# iot_inventory_mote.net
KiCad netlist of a schematic drawn in EAGLE
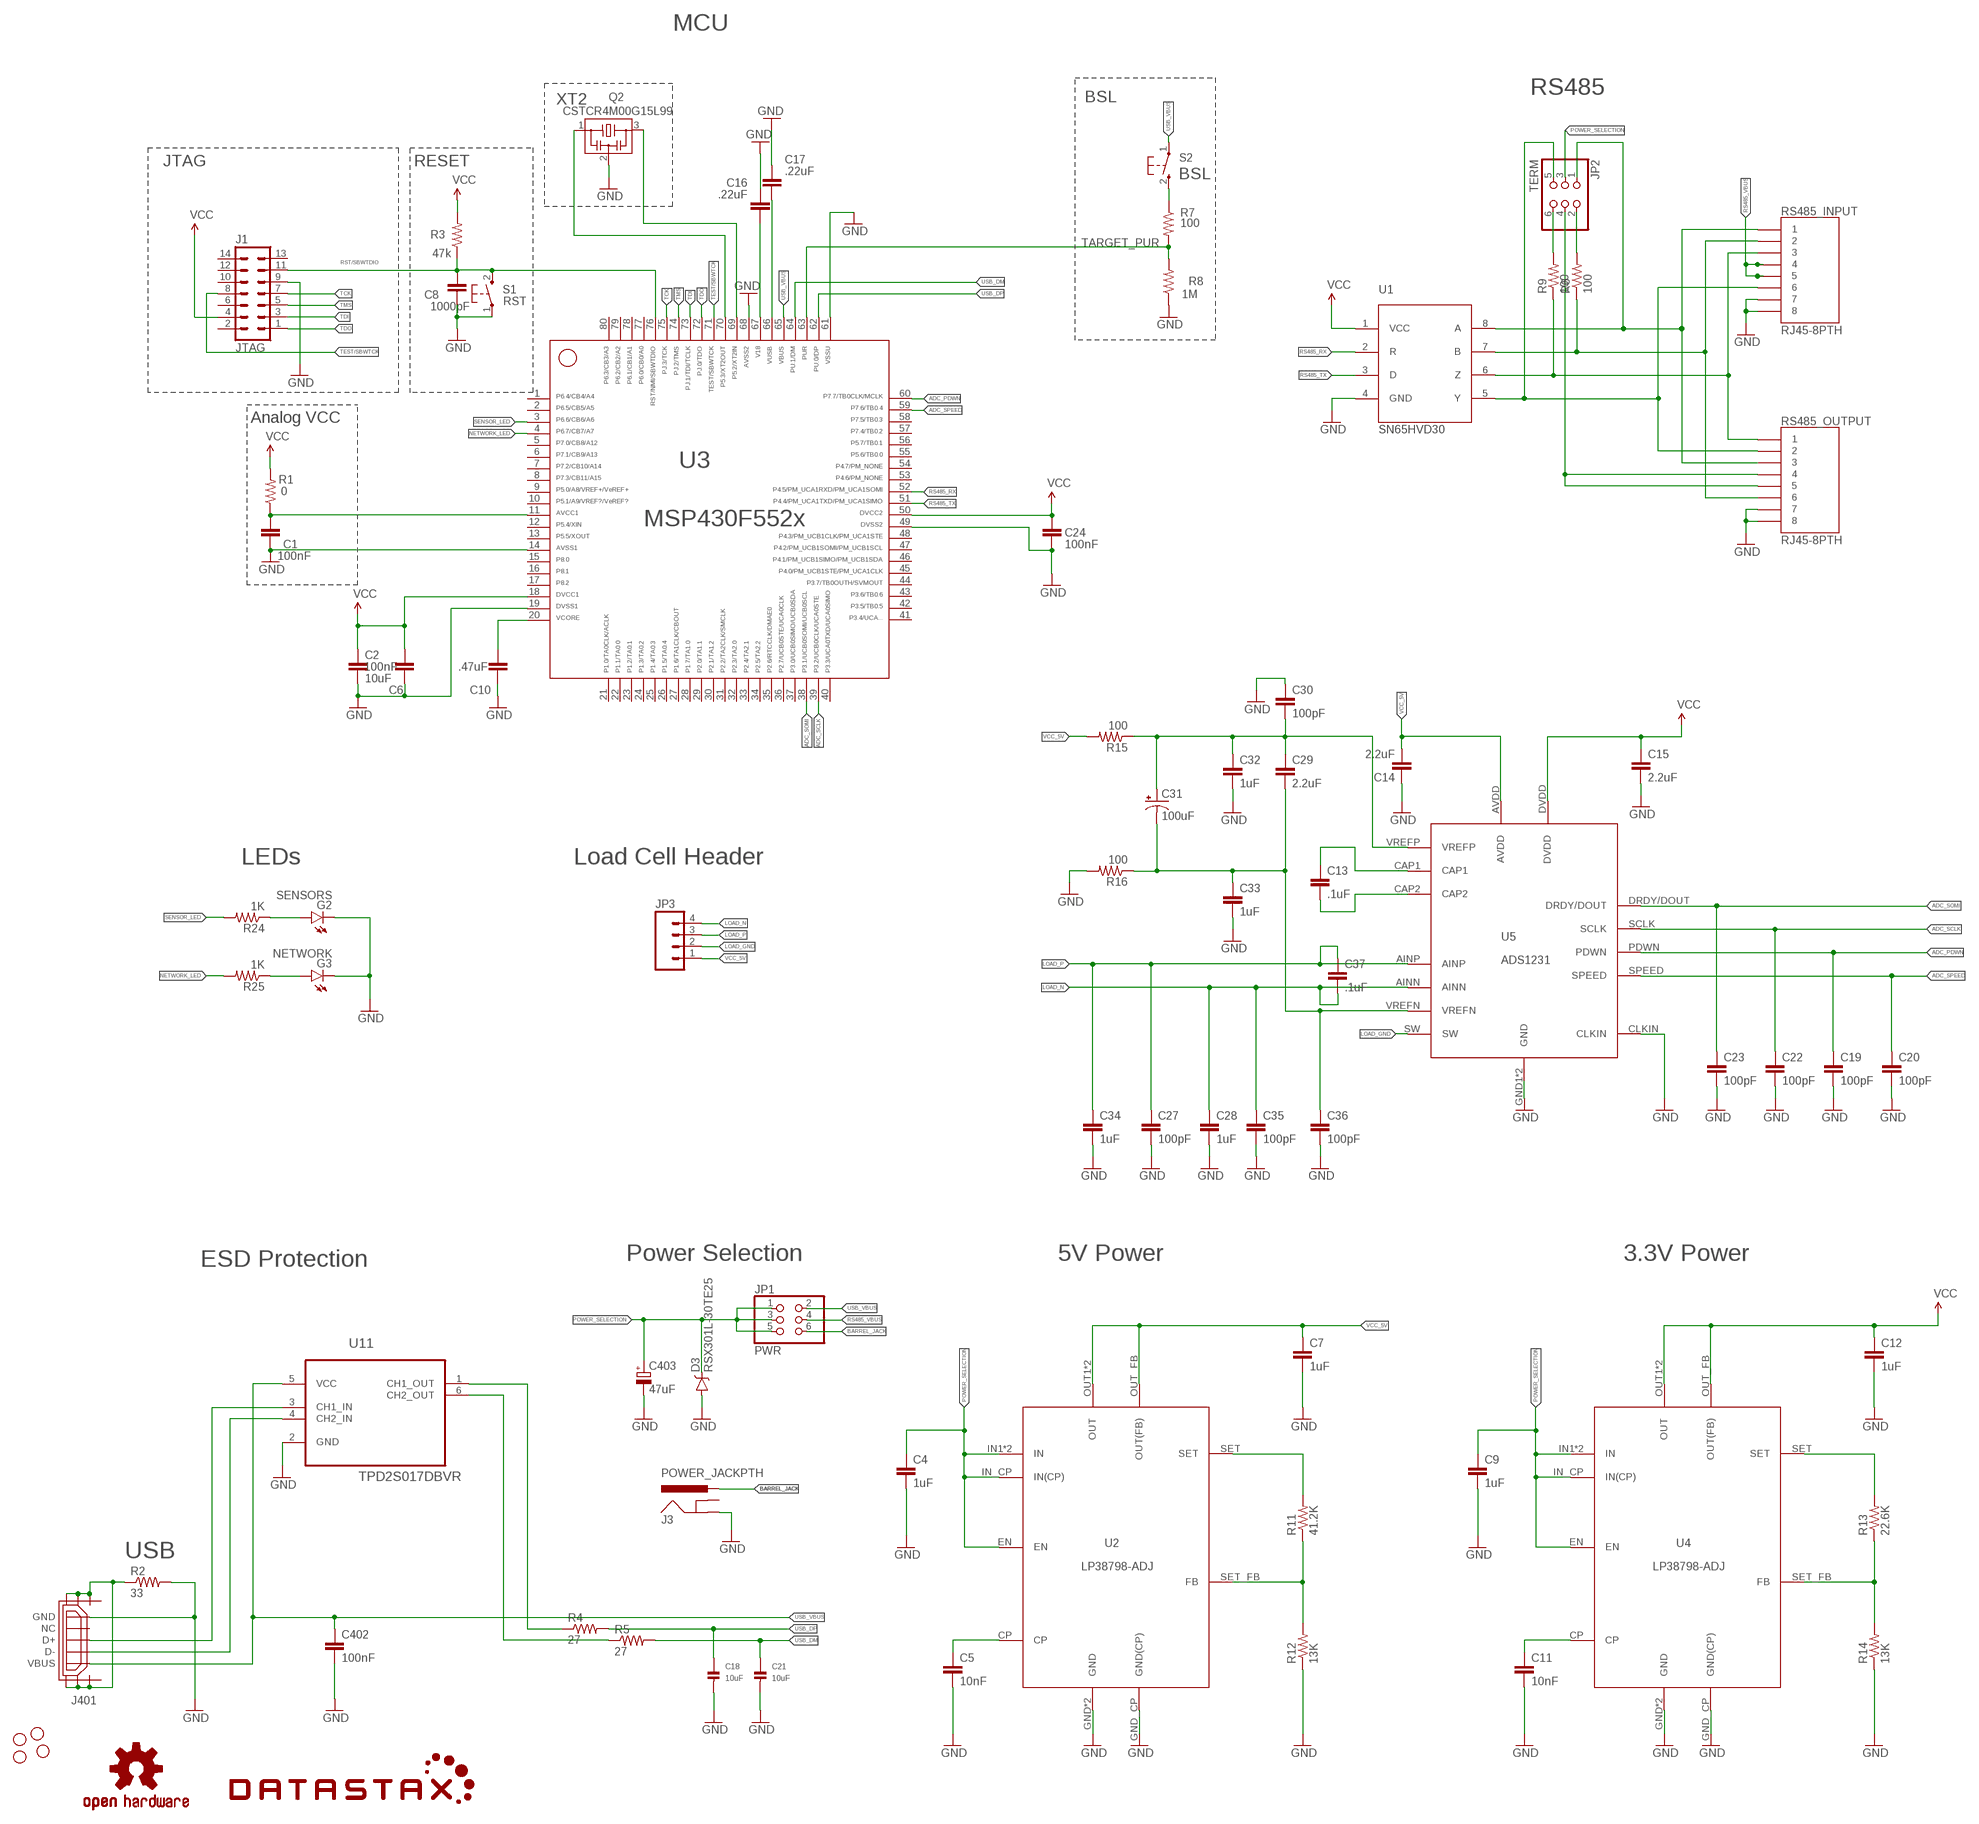
[diagram p0: schematic, sheet 1]

(export (version "E")
  (design (tool "Eeschema 10.0.6"))
  (components
    (comp (ref "C1")
      (value "100nF")
      (footprint "eagle-import:0402-CAP")
      (libsource (lib "eagle-import") (part "CAP0402-CAP"))
    )
    (comp (ref "C2")
      (value "10uF")
      (footprint "eagle-import:0402-CAP")
      (libsource (lib "eagle-import") (part "CAP0402-CAP"))
    )
    (comp (ref "C4")
      (value "1uF")
      (footprint "eagle-import:0402-CAP")
      (libsource (lib "eagle-import") (part "CAP0402-CAP"))
    )
    (comp (ref "C5")
      (value "10nF")
      (footprint "eagle-import:0402-CAP")
      (libsource (lib "eagle-import") (part "CAP0402-CAP"))
    )
    (comp (ref "C6")
      (value "100nF")
      (footprint "eagle-import:0402-CAP")
      (libsource (lib "eagle-import") (part "CAP0402-CAP"))
    )
    (comp (ref "C7")
      (value "1uF")
      (footprint "eagle-import:0402-CAP")
      (libsource (lib "eagle-import") (part "CAP0402-CAP"))
    )
    (comp (ref "C8")
      (value "1000pF")
      (footprint "eagle-import:0402-CAP")
      (fields (field (name "MF") "TDK") (field (name "MPN") "C1005X7R1H102K050BA"))
      (libsource (lib "eagle-import") (part "CAP0402-CAP"))
    )
    (comp (ref "C9")
      (value "1uF")
      (footprint "eagle-import:0402-CAP")
      (libsource (lib "eagle-import") (part "CAP0402-CAP"))
    )
    (comp (ref "C10")
      (value ".47uF")
      (footprint "eagle-import:0402-CAP")
      (libsource (lib "eagle-import") (part "CAP0402-CAP"))
    )
    (comp (ref "C11")
      (value "10nF")
      (footprint "eagle-import:0402-CAP")
      (libsource (lib "eagle-import") (part "CAP0402-CAP"))
    )
    (comp (ref "C12")
      (value "1uF")
      (footprint "eagle-import:0402-CAP")
      (libsource (lib "eagle-import") (part "CAP0402-CAP"))
    )
    (comp (ref "C13")
      (value ".1uF")
      (footprint "eagle-import:1210")
      (libsource (lib "eagle-import") (part "CAP1210"))
    )
    (comp (ref "C14")
      (value "2.2uF")
      (footprint "eagle-import:0402-CAP")
      (libsource (lib "eagle-import") (part "CAP0402-CAP"))
    )
    (comp (ref "C15")
      (value "2.2uF")
      (footprint "eagle-import:0402-CAP")
      (libsource (lib "eagle-import") (part "CAP0402-CAP"))
    )
    (comp (ref "C16")
      (value ".22uF")
      (footprint "eagle-import:0402-CAP")
      (libsource (lib "eagle-import") (part "CAP0402-CAP"))
    )
    (comp (ref "C17")
      (value ".22uF")
      (footprint "eagle-import:0402-CAP")
      (libsource (lib "eagle-import") (part "CAP0402-CAP"))
    )
    (comp (ref "C18")
      (value "10uF")
      (footprint "eagle-import:0603")
      (fields (field (name "MPN") "06035A100FAT2A"))
      (libsource (lib "eagle-import") (part "CAP_CERAMIC0603"))
    )
    (comp (ref "C19")
      (value "100pF")
      (footprint "eagle-import:0805")
      (libsource (lib "eagle-import") (part "CAP0805"))
    )
    (comp (ref "C20")
      (value "100pF")
      (footprint "eagle-import:0805")
      (libsource (lib "eagle-import") (part "CAP0805"))
    )
    (comp (ref "C21")
      (value "10uF")
      (footprint "eagle-import:0603")
      (fields (field (name "MPN") "06035A100FAT2A"))
      (libsource (lib "eagle-import") (part "CAP_CERAMIC0603"))
    )
    (comp (ref "C22")
      (value "100pF")
      (footprint "eagle-import:0805")
      (libsource (lib "eagle-import") (part "CAP0805"))
    )
    (comp (ref "C23")
      (value "100pF")
      (footprint "eagle-import:0805")
      (libsource (lib "eagle-import") (part "CAP0805"))
    )
    (comp (ref "C24")
      (value "100nF")
      (footprint "eagle-import:0402-CAP")
      (libsource (lib "eagle-import") (part "CAP0402-CAP"))
    )
    (comp (ref "C27")
      (value "100pF")
      (footprint "eagle-import:0603-CAP")
      (libsource (lib "eagle-import") (part "CAP0603-CAP"))
    )
    (comp (ref "C28")
      (value "1uF")
      (footprint "eagle-import:0805")
      (libsource (lib "eagle-import") (part "CAP0805"))
    )
    (comp (ref "C29")
      (value "2.2uF")
      (footprint "eagle-import:0402-CAP")
      (libsource (lib "eagle-import") (part "CAP0402-CAP"))
    )
    (comp (ref "C30")
      (value "100pF")
      (footprint "eagle-import:0603-CAP")
      (libsource (lib "eagle-import") (part "CAP0603-CAP"))
    )
    (comp (ref "C31")
      (value "100uF")
      (footprint "eagle-import:EIA7343")
      (libsource (lib "eagle-import") (part "CAP_POL7343"))
    )
    (comp (ref "C32")
      (value "1uF")
      (footprint "eagle-import:0805")
      (libsource (lib "eagle-import") (part "CAP0805"))
    )
    (comp (ref "C33")
      (value "1uF")
      (footprint "eagle-import:0805")
      (libsource (lib "eagle-import") (part "CAP0805"))
    )
    (comp (ref "C34")
      (value "1uF")
      (footprint "eagle-import:0805")
      (libsource (lib "eagle-import") (part "CAP0805"))
    )
    (comp (ref "C35")
      (value "100pF")
      (footprint "eagle-import:0603-CAP")
      (libsource (lib "eagle-import") (part "CAP0603-CAP"))
    )
    (comp (ref "C36")
      (value "100pF")
      (footprint "eagle-import:0603-CAP")
      (libsource (lib "eagle-import") (part "CAP0603-CAP"))
    )
    (comp (ref "C37")
      (value ".1uF")
      (footprint "eagle-import:1210")
      (libsource (lib "eagle-import") (part "CAP1210"))
    )
    (comp (ref "C402")
      (value "100nF")
      (footprint "eagle-import:0402-CAP")
      (fields (field (name "MPN") "100NA100MEFC12.5X25"))
      (libsource (lib "eagle-import") (part "CAP0402-CAP"))
    )
    (comp (ref "C403")
      (value "47uF")
      (footprint "eagle-import:A_3216-18R")
      (libsource (lib "eagle-import") (part "CPOL-EUA/3216-18R"))
    )
    (comp (ref "D3")
      (value "RSX301L-30TE25")
      (footprint "eagle-import:SMA-DIODE")
      (libsource (lib "eagle-import") (part "MBRA140"))
    )
    (comp (ref "G2")
      (value "SENSORS")
      (footprint "eagle-import:LED-0603")
      (libsource (lib "eagle-import") (part "LED0603"))
    )
    (comp (ref "G3")
      (value "NETWORK")
      (footprint "eagle-import:LED-0603")
      (libsource (lib "eagle-import") (part "LED0603"))
    )
    (comp (ref "J1")
      (value "JTAG")
      (footprint "eagle-import:ML14")
      (fields (field (name "MF") "SULLINS") (field (name "MPN") "SBH11-PBPC-D07-ST-BK"))
      (libsource (lib "eagle-import") (part "ML14"))
    )
    (comp (ref "J3")
      (value "POWER_JACKPTH")
      (footprint "eagle-import:POWER_JACK_PTH")
      (libsource (lib "eagle-import") (part "POWER_JACKPTH"))
    )
    (comp (ref "J401")
      (value "USB_MICRO_FLIPPED")
      (footprint "eagle-import:HIROSE-ZX62R-B-5P")
      (fields (field (name "MF") "HIROSE") (field (name "MPN") "ZX62R-B-5P"))
      (libsource (lib "eagle-import") (part "USB_MICRO_FLIPPED"))
    )
    (comp (ref "JP1")
      (value "PWR")
      (footprint "eagle-import:2X03")
      (libsource (lib "eagle-import") (part "PINHD-2X3"))
    )
    (comp (ref "JP2")
      (value "TERM")
      (footprint "eagle-import:2X03")
      (libsource (lib "eagle-import") (part "PINHD-2X3"))
    )
    (comp (ref "JP3")
      (value "M04SCREW")
      (footprint "eagle-import:SCREWTERMINAL-3.5MM-4")
      (libsource (lib "eagle-import") (part "M04SCREW"))
    )
    (comp (ref "LOGO1")
      (value "OSHW-LOGOL")
      (footprint "eagle-import:OSHW-LOGO-L")
      (libsource (lib "eagle-import") (part "OSHW-LOGOL"))
    )
    (comp (ref "Q2")
      (value "CSTCR4M00G15L99")
      (footprint "eagle-import:MURATA-FILTER_CSTCR")
      (fields (field (name "MPN") "CSTCR6M00G53-R0") (field (name "MF") "MURATA"))
      (libsource (lib "eagle-import") (part "MURATA-FILTER_CSTCR6M00G53Z"))
    )
    (comp (ref "R1")
      (value "0")
      (footprint "eagle-import:R0402")
      (libsource (lib "eagle-import") (part "R-US_R0402"))
    )
    (comp (ref "R2")
      (value "33")
      (footprint "eagle-import:0402-RES")
      (libsource (lib "eagle-import") (part "RESISTOR0402-RES"))
    )
    (comp (ref "R3")
      (value "47k")
      (footprint "eagle-import:R0402")
      (fields (field (name "MF") "PANASONIC ") (field (name "MPN") "ERJ-2RKF4702X"))
      (libsource (lib "eagle-import") (part "R-US_R0402"))
    )
    (comp (ref "R4")
      (value "27")
      (footprint "eagle-import:0402-RES")
      (libsource (lib "eagle-import") (part "RESISTOR0402-RES"))
    )
    (comp (ref "R5")
      (value "27")
      (footprint "eagle-import:0402-RES")
      (libsource (lib "eagle-import") (part "RESISTOR0402-RES"))
    )
    (comp (ref "R6")
      (value "100")
      (footprint "eagle-import:0402-RES")
      (libsource (lib "eagle-import") (part "RESISTOR0402-RES"))
    )
    (comp (ref "R7")
      (value "100")
      (footprint "eagle-import:R0402")
      (libsource (lib "eagle-import") (part "R-US_R0402"))
    )
    (comp (ref "R8")
      (value "1M")
      (footprint "eagle-import:R0402")
      (libsource (lib "eagle-import") (part "R-US_R0402"))
    )
    (comp (ref "R9")
      (value "100")
      (footprint "eagle-import:0402-RES")
      (libsource (lib "eagle-import") (part "RESISTOR0402-RES"))
    )
    (comp (ref "R11")
      (value "41.2K")
      (footprint "eagle-import:0402-RES")
      (libsource (lib "eagle-import") (part "RESISTOR0402-RES"))
    )
    (comp (ref "R12")
      (value "13K")
      (footprint "eagle-import:0402-RES")
      (libsource (lib "eagle-import") (part "RESISTOR0402-RES"))
    )
    (comp (ref "R13")
      (value "22.6K")
      (footprint "eagle-import:0402-RES")
      (libsource (lib "eagle-import") (part "RESISTOR0402-RES"))
    )
    (comp (ref "R14")
      (value "13K")
      (footprint "eagle-import:0402-RES")
      (libsource (lib "eagle-import") (part "RESISTOR0402-RES"))
    )
    (comp (ref "R15")
      (value "100")
      (footprint "eagle-import:0402-RES")
      (libsource (lib "eagle-import") (part "RESISTOR0402-RES"))
    )
    (comp (ref "R16")
      (value "100")
      (footprint "eagle-import:0402-RES")
      (libsource (lib "eagle-import") (part "RESISTOR0402-RES"))
    )
    (comp (ref "R24")
      (value "1K")
      (footprint "eagle-import:0402-RES")
      (fields (field (name "MF") "PANASONIC") (field (name "MPN") "ERJ-2RKF1001X"))
      (libsource (lib "eagle-import") (part "RESISTOR0402-RES"))
    )
    (comp (ref "R25")
      (value "1K")
      (footprint "eagle-import:0402-RES")
      (fields (field (name "MF") "PANASONIC") (field (name "MPN") "ERJ-2RKF1001X"))
      (libsource (lib "eagle-import") (part "RESISTOR0402-RES"))
    )
    (comp (ref "RS485_INPUT")
      (value "RJ45-8PTH")
      (footprint "eagle-import:RJ45-8")
      (fields (field (name "MF") "FCI") (field (name "MPN") "54602-908LF"))
      (libsource (lib "eagle-import") (part "RJ45-8PTH"))
    )
    (comp (ref "RS485_OUTPUT")
      (value "RJ45-8PTH")
      (footprint "eagle-import:RJ45-8")
      (fields (field (name "MF") "FCI") (field (name "MPN") "54602-908LF"))
      (libsource (lib "eagle-import") (part "RJ45-8PTH"))
    )
    (comp (ref "S1")
      (value "RST")
      (footprint "eagle-import:PBTH")
      (fields (field (name "MF") "PANASONIC ") (field (name "MPN") "EVQ-11L05R"))
      (libsource (lib "eagle-import") (part "PB"))
    )
    (comp (ref "S2")
      (value "BSL")
      (footprint "eagle-import:PBTH")
      (libsource (lib "eagle-import") (part "PB"))
    )
    (comp (ref "STANDOFF1")
      (value "STAND-OFF")
      (footprint "eagle-import:STAND-OFF")
      (libsource (lib "eagle-import") (part "STAND-OFF"))
    )
    (comp (ref "STANDOFF2")
      (value "STAND-OFF")
      (footprint "eagle-import:STAND-OFF")
      (libsource (lib "eagle-import") (part "STAND-OFF"))
    )
    (comp (ref "STANDOFF3")
      (value "STAND-OFF")
      (footprint "eagle-import:STAND-OFF")
      (libsource (lib "eagle-import") (part "STAND-OFF"))
    )
    (comp (ref "STANDOFF4")
      (value "STAND-OFF")
      (footprint "eagle-import:STAND-OFF")
      (libsource (lib "eagle-import") (part "STAND-OFF"))
    )
    (comp (ref "U$1")
      (value "DATASTAX_LOGO")
      (footprint "eagle-import:DATASTAX_LOGO")
      (libsource (lib "eagle-import") (part "DATASTAX_LOGO"))
    )
    (comp (ref "U1")
      (value "SN65HVD30")
      (footprint "eagle-import:SOIC8")
      (fields (field (name "MF") "TI") (field (name "MPN") "SN65HVD3082EDR"))
      (libsource (lib "eagle-import") (part "SN65HVD30"))
    )
    (comp (ref "U2")
      (value "LP38798-ADJ")
      (footprint "eagle-import:WSON12")
      (fields (field (name "MF") "TI") (field (name "MPN") "LP38798SD-ADJ/NOPB"))
      (libsource (lib "eagle-import") (part "LP38798-ADJ"))
    )
    (comp (ref "U3")
      (value "MSP430F5529IPNR")
      (footprint "eagle-import:PN80")
      (fields (field (name "MF") "TI"))
      (libsource (lib "eagle-import") (part "F552X---PN80"))
    )
    (comp (ref "U4")
      (value "LP38798-ADJ")
      (footprint "eagle-import:WSON12")
      (fields (field (name "MF") "TI") (field (name "MPN") "LP38798SD-ADJ/NOPB"))
      (libsource (lib "eagle-import") (part "LP38798-ADJ"))
    )
    (comp (ref "U5")
      (value "ADS1231")
      (footprint "eagle-import:ADS1231")
      (fields (field (name "MF") "TI") (field (name "MPN") "ADS1231ID"))
      (libsource (lib "eagle-import") (part "ADS1231"))
    )
    (comp (ref "U11")
      (value "TPD2S017DBVR")
      (footprint "eagle-import:SOT95P280X145-6N")
      (fields (field (name "MF") "TI"))
      (libsource (lib "eagle-import") (part "TPD2S017DBVR"))
    )
  )
  (nets
    (net (code "1") (name "ADC_PDWN") (class "Default")
      (node (ref "C19") (pin "1") (pinfunction "1_1") (pintype "passive"))
      (node (ref "U3") (pin "60") (pinfunction "60_60") (pintype "bidirectional"))
      (node (ref "U5") (pin "PDWN") (pinfunction "PDWN_PDWN") (pintype "input"))
    )
    (net (code "2") (name "ADC_SCLK") (class "Default")
      (node (ref "C22") (pin "1") (pinfunction "1_1") (pintype "passive"))
      (node (ref "U3") (pin "39") (pinfunction "39_39") (pintype "bidirectional"))
      (node (ref "U5") (pin "SCLK") (pinfunction "SCLK_SCLK") (pintype "input"))
    )
    (net (code "3") (name "ADC_SOMI") (class "Default")
      (node (ref "C23") (pin "1") (pinfunction "1_1") (pintype "passive"))
      (node (ref "U3") (pin "38") (pinfunction "38_38") (pintype "bidirectional"))
      (node (ref "U5") (pin "DRDY/DOUT") (pinfunction "DRDY/DOUT_DRDY/DOUT") (pintype "output"))
    )
    (net (code "4") (name "ADC_SPEED") (class "Default")
      (node (ref "C20") (pin "1") (pinfunction "1_1") (pintype "passive"))
      (node (ref "U3") (pin "59") (pinfunction "59_59") (pintype "bidirectional"))
      (node (ref "U5") (pin "SPEED") (pinfunction "SPEED_SPEED") (pintype "input"))
    )
    (net (code "5") (name "BARREL_JACK") (class "Default")
      (node (ref "J3") (pin "PWR") (pinfunction "PWR_PWR") (pintype "bidirectional"))
      (node (ref "JP1") (pin "6") (pinfunction "6_6") (pintype "passive"))
    )
    (net (code "6") (name "GND") (class "Default")
      (node (ref "C1") (pin "2") (pinfunction "2_2") (pintype "passive"))
      (node (ref "C10") (pin "2") (pinfunction "2_2") (pintype "passive"))
      (node (ref "C11") (pin "2") (pinfunction "2_2") (pintype "passive"))
      (node (ref "C12") (pin "2") (pinfunction "2_2") (pintype "passive"))
      (node (ref "C14") (pin "1") (pinfunction "1_1") (pintype "passive"))
      (node (ref "C15") (pin "2") (pinfunction "2_2") (pintype "passive"))
      (node (ref "C16") (pin "2") (pinfunction "2_2") (pintype "passive"))
      (node (ref "C17") (pin "2") (pinfunction "2_2") (pintype "passive"))
      (node (ref "C18") (pin "2") (pinfunction "P$2_2") (pintype "passive"))
      (node (ref "C19") (pin "2") (pinfunction "2_2") (pintype "passive"))
      (node (ref "C2") (pin "2") (pinfunction "2_2") (pintype "passive"))
      (node (ref "C20") (pin "2") (pinfunction "2_2") (pintype "passive"))
      (node (ref "C21") (pin "2") (pinfunction "P$2_2") (pintype "passive"))
      (node (ref "C22") (pin "2") (pinfunction "2_2") (pintype "passive"))
      (node (ref "C23") (pin "2") (pinfunction "2_2") (pintype "passive"))
      (node (ref "C24") (pin "2") (pinfunction "2_2") (pintype "passive"))
      (node (ref "C27") (pin "2") (pinfunction "2_2") (pintype "passive"))
      (node (ref "C28") (pin "2") (pinfunction "2_2") (pintype "passive"))
      (node (ref "C30") (pin "1") (pinfunction "1_1") (pintype "passive"))
      (node (ref "C32") (pin "2") (pinfunction "2_2") (pintype "passive"))
      (node (ref "C33") (pin "2") (pinfunction "2_2") (pintype "passive"))
      (node (ref "C34") (pin "2") (pinfunction "2_2") (pintype "passive"))
      (node (ref "C35") (pin "2") (pinfunction "2_2") (pintype "passive"))
      (node (ref "C36") (pin "2") (pinfunction "2_2") (pintype "passive"))
      (node (ref "C4") (pin "2") (pinfunction "2_2") (pintype "passive"))
      (node (ref "C402") (pin "2") (pinfunction "2_2") (pintype "passive"))
      (node (ref "C403") (pin "-") (pinfunction "-_-") (pintype "passive"))
      (node (ref "C5") (pin "2") (pinfunction "2_2") (pintype "passive"))
      (node (ref "C6") (pin "2") (pinfunction "2_2") (pintype "passive"))
      (node (ref "C7") (pin "2") (pinfunction "2_2") (pintype "passive"))
      (node (ref "C8") (pin "2") (pinfunction "2_2") (pintype "passive"))
      (node (ref "C9") (pin "2") (pinfunction "2_2") (pintype "passive"))
      (node (ref "D3") (pin "A") (pinfunction "A_A") (pintype "passive"))
      (node (ref "G2") (pin "C") (pinfunction "C_C") (pintype "passive"))
      (node (ref "G3") (pin "C") (pinfunction "C_C") (pintype "passive"))
      (node (ref "J1") (pin "9") (pinfunction "9_9") (pintype "passive"))
      (node (ref "J3") (pin "GND") (pinfunction "GND_GND") (pintype "bidirectional"))
      (node (ref "J401") (pin "GND") (pinfunction "GND_GND") (pintype "input"))
      (node (ref "Q2") (pin "2") (pinfunction "2_2") (pintype "passive"))
      (node (ref "R12") (pin "1") (pinfunction "1_1") (pintype "passive"))
      (node (ref "R14") (pin "1") (pinfunction "1_1") (pintype "passive"))
      (node (ref "R16") (pin "2") (pinfunction "2_2") (pintype "passive"))
      (node (ref "R2") (pin "2") (pinfunction "2_2") (pintype "passive"))
      (node (ref "R8") (pin "1") (pinfunction "1_1") (pintype "passive"))
      (node (ref "RS485_INPUT") (pin "7") (pinfunction "7_7") (pintype "bidirectional"))
      (node (ref "RS485_INPUT") (pin "8") (pinfunction "8_8") (pintype "bidirectional"))
      (node (ref "RS485_OUTPUT") (pin "7") (pinfunction "7_7") (pintype "bidirectional"))
      (node (ref "RS485_OUTPUT") (pin "8") (pinfunction "8_8") (pintype "bidirectional"))
      (node (ref "S1") (pin "1") (pinfunction "P_1") (pintype "passive"))
      (node (ref "U1") (pin "4") (pinfunction "GND_4") (pintype "power_in"))
      (node (ref "U11") (pin "2") (pinfunction "GND_2") (pintype "passive"))
      (node (ref "U2") (pin "GND") (pinfunction "GND_GND") (pintype "power_in"))
      (node (ref "U2") (pin "GND_CP") (pinfunction "GND(CP)_GND_CP") (pintype "power_in"))
      (node (ref "U2") (pin "GPAD") (pinfunction "GND_GPAD") (pintype "power_in"))
      (node (ref "U3") (pin "14") (pinfunction "14_14") (pintype "power_in"))
      (node (ref "U3") (pin "19") (pinfunction "19_19") (pintype "power_in"))
      (node (ref "U3") (pin "49") (pinfunction "49_49") (pintype "power_in"))
      (node (ref "U3") (pin "61") (pinfunction "61_61") (pintype "power_in"))
      (node (ref "U3") (pin "68") (pinfunction "68_68") (pintype "power_in"))
      (node (ref "U4") (pin "GND") (pinfunction "GND_GND") (pintype "power_in"))
      (node (ref "U4") (pin "GND_CP") (pinfunction "GND(CP)_GND_CP") (pintype "power_in"))
      (node (ref "U4") (pin "GPAD") (pinfunction "GND_GPAD") (pintype "power_in"))
      (node (ref "U5") (pin "CLKIN") (pinfunction "CLKIN_CLKIN") (pintype "input"))
      (node (ref "U5") (pin "GND1") (pinfunction "GND_GND1") (pintype "power_in"))
      (node (ref "U5") (pin "GND2") (pinfunction "GND_GND2") (pintype "power_in"))
    )
    (net (code "7") (name "LOAD_GND") (class "Default")
      (node (ref "JP3") (pin "2") (pinfunction "2_2") (pintype "passive"))
      (node (ref "U5") (pin "SW") (pinfunction "SW_SW") (pintype "passive"))
    )
    (net (code "8") (name "LOAD_N") (class "Default")
      (node (ref "C28") (pin "1") (pinfunction "1_1") (pintype "passive"))
      (node (ref "C35") (pin "1") (pinfunction "1_1") (pintype "passive"))
      (node (ref "C37") (pin "2") (pinfunction "2_2") (pintype "passive"))
      (node (ref "JP3") (pin "4") (pinfunction "4_4") (pintype "passive"))
      (node (ref "U5") (pin "AINN") (pinfunction "AINN_AINN") (pintype "input"))
    )
    (net (code "9") (name "LOAD_P") (class "Default")
      (node (ref "C27") (pin "1") (pinfunction "1_1") (pintype "passive"))
      (node (ref "C34") (pin "1") (pinfunction "1_1") (pintype "passive"))
      (node (ref "C37") (pin "1") (pinfunction "1_1") (pintype "passive"))
      (node (ref "JP3") (pin "3") (pinfunction "3_3") (pintype "passive"))
      (node (ref "U5") (pin "AINP") (pinfunction "AINP_AINP") (pintype "input"))
    )
    (net (code "10") (name "NETWORK_LED") (class "Default")
      (node (ref "R25") (pin "2") (pinfunction "2_2") (pintype "passive"))
      (node (ref "U3") (pin "4") (pinfunction "4_4") (pintype "bidirectional"))
    )
    (net (code "11") (name "Net-(C1-Pad1)") (class "Default")
      (node (ref "C1") (pin "1") (pinfunction "1_1") (pintype "passive"))
      (node (ref "R1") (pin "1") (pinfunction "1_1") (pintype "passive"))
      (node (ref "U3") (pin "11") (pinfunction "11_11") (pintype "power_in"))
    )
    (net (code "12") (name "Net-(C5-Pad1)") (class "Default")
      (node (ref "C5") (pin "1") (pinfunction "1_1") (pintype "passive"))
      (node (ref "U2") (pin "CP") (pinfunction "CP_CP") (pintype "passive"))
    )
    (net (code "13") (name "Net-(C10-Pad1)") (class "Default")
      (node (ref "C10") (pin "1") (pinfunction "1_1") (pintype "passive"))
      (node (ref "U3") (pin "20") (pinfunction "20_20") (pintype "power_in"))
    )
    (net (code "14") (name "Net-(C11-Pad1)") (class "Default")
      (node (ref "C11") (pin "1") (pinfunction "1_1") (pintype "passive"))
      (node (ref "U4") (pin "CP") (pinfunction "CP_CP") (pintype "passive"))
    )
    (net (code "15") (name "Net-(C13-Pad1)") (class "Default")
      (node (ref "C13") (pin "1") (pinfunction "1_1") (pintype "passive"))
      (node (ref "U5") (pin "CAP1") (pinfunction "CAP1_CAP1") (pintype "passive"))
    )
    (net (code "16") (name "Net-(C13-Pad2)") (class "Default")
      (node (ref "C13") (pin "2") (pinfunction "2_2") (pintype "passive"))
      (node (ref "U5") (pin "CAP2") (pinfunction "CAP2_CAP2") (pintype "passive"))
    )
    (net (code "17") (name "Net-(C16-Pad1)") (class "Default")
      (node (ref "C16") (pin "1") (pinfunction "1_1") (pintype "passive"))
      (node (ref "U3") (pin "67") (pinfunction "67_67") (pintype "power_in"))
    )
    (net (code "18") (name "Net-(C17-Pad1)") (class "Default")
      (node (ref "C17") (pin "1") (pinfunction "1_1") (pintype "passive"))
      (node (ref "U3") (pin "66") (pinfunction "66_66") (pintype "power_in"))
    )
    (net (code "19") (name "Net-(C31-+)") (class "Default")
      (node (ref "C29") (pin "1") (pinfunction "1_1") (pintype "passive"))
      (node (ref "C30") (pin "2") (pinfunction "2_2") (pintype "passive"))
      (node (ref "C31") (pin "A") (pinfunction "+_A") (pintype "passive"))
      (node (ref "C32") (pin "1") (pinfunction "1_1") (pintype "passive"))
      (node (ref "R15") (pin "1") (pinfunction "1_1") (pintype "passive"))
      (node (ref "U5") (pin "VREFP") (pinfunction "VREFP_VREFP") (pintype "passive"))
    )
    (net (code "20") (name "Net-(C31--)") (class "Default")
      (node (ref "C29") (pin "2") (pinfunction "2_2") (pintype "passive"))
      (node (ref "C31") (pin "C") (pinfunction "-_C") (pintype "passive"))
      (node (ref "C33") (pin "1") (pinfunction "1_1") (pintype "passive"))
      (node (ref "C36") (pin "1") (pinfunction "1_1") (pintype "passive"))
      (node (ref "R16") (pin "1") (pinfunction "1_1") (pintype "passive"))
      (node (ref "U5") (pin "VREFN") (pinfunction "VREFN_VREFN") (pintype "passive"))
    )
    (net (code "21") (name "Net-(G2-PadA)") (class "Default")
      (node (ref "G2") (pin "A") (pinfunction "A_A") (pintype "passive"))
      (node (ref "R24") (pin "1") (pinfunction "1_1") (pintype "passive"))
    )
    (net (code "22") (name "Net-(G3-PadA)") (class "Default")
      (node (ref "G3") (pin "A") (pinfunction "A_A") (pintype "passive"))
      (node (ref "R25") (pin "1") (pinfunction "1_1") (pintype "passive"))
    )
    (net (code "23") (name "Net-(J401-PadSHIELD1)") (class "Default")
      (node (ref "J401") (pin "SHIELD1") (pinfunction "SHIELD1_SHIELD1") (pintype "bidirectional"))
      (node (ref "J401") (pin "SHIELD2") (pinfunction "SHIELD2_SHIELD2") (pintype "bidirectional"))
      (node (ref "J401") (pin "SHIELD3") (pinfunction "SHIELD3_SHIELD3") (pintype "bidirectional"))
      (node (ref "J401") (pin "SHIELD4") (pinfunction "SHIELD4_SHIELD4") (pintype "bidirectional"))
      (node (ref "J401") (pin "SHIELD5") (pinfunction "SHIELD5_SHIELD5") (pintype "bidirectional"))
      (node (ref "J401") (pin "SHIELD6") (pinfunction "SHIELD6_SHIELD6") (pintype "bidirectional"))
      (node (ref "R2") (pin "1") (pinfunction "1_1") (pintype "passive"))
    )
    (net (code "24") (name "Net-(JP2-Pad2)") (class "Default")
      (node (ref "JP2") (pin "2") (pinfunction "2_2") (pintype "passive"))
      (node (ref "R6") (pin "2") (pinfunction "2_2") (pintype "passive"))
    )
    (net (code "25") (name "Net-(JP2-Pad4)") (class "Default")
      (node (ref "JP2") (pin "4") (pinfunction "4_4") (pintype "passive"))
      (node (ref "RS485_OUTPUT") (pin "4") (pinfunction "4_4") (pintype "bidirectional"))
      (node (ref "RS485_OUTPUT") (pin "5") (pinfunction "5_5") (pintype "bidirectional"))
    )
    (net (code "26") (name "Net-(JP2-Pad6)") (class "Default")
      (node (ref "JP2") (pin "6") (pinfunction "6_6") (pintype "passive"))
      (node (ref "R9") (pin "2") (pinfunction "2_2") (pintype "passive"))
    )
    (net (code "27") (name "Net-(Q2-Pad1)") (class "Default")
      (node (ref "Q2") (pin "1") (pinfunction "1_1") (pintype "passive"))
      (node (ref "U3") (pin "70") (pinfunction "70_70") (pintype "bidirectional"))
    )
    (net (code "28") (name "Net-(Q2-Pad3)") (class "Default")
      (node (ref "Q2") (pin "3") (pinfunction "3_3") (pintype "passive"))
      (node (ref "U3") (pin "69") (pinfunction "69_69") (pintype "bidirectional"))
    )
    (net (code "29") (name "Net-(R11-Pad2)") (class "Default")
      (node (ref "R11") (pin "2") (pinfunction "2_2") (pintype "passive"))
      (node (ref "U2") (pin "SET") (pinfunction "SET_SET") (pintype "passive"))
    )
    (net (code "30") (name "Net-(R13-Pad2)") (class "Default")
      (node (ref "R13") (pin "2") (pinfunction "2_2") (pintype "passive"))
      (node (ref "U4") (pin "SET") (pinfunction "SET_SET") (pintype "passive"))
    )
    (net (code "31") (name "Net-(S2-S)") (class "Default")
      (node (ref "R7") (pin "1") (pinfunction "1_1") (pintype "passive"))
      (node (ref "S2") (pin "2") (pinfunction "S_2") (pintype "passive"))
    )
    (net (code "32") (name "Net-(U1-A)") (class "Default")
      (node (ref "JP2") (pin "1") (pinfunction "1_1") (pintype "passive"))
      (node (ref "RS485_INPUT") (pin "1") (pinfunction "1_1") (pintype "bidirectional"))
      (node (ref "RS485_OUTPUT") (pin "3") (pinfunction "3_3") (pintype "bidirectional"))
      (node (ref "U1") (pin "8") (pinfunction "A_8") (pintype "input"))
    )
    (net (code "33") (name "Net-(U1-B)") (class "Default")
      (node (ref "R6") (pin "1") (pinfunction "1_1") (pintype "passive"))
      (node (ref "RS485_INPUT") (pin "2") (pinfunction "2_2") (pintype "bidirectional"))
      (node (ref "RS485_OUTPUT") (pin "6") (pinfunction "6_6") (pintype "bidirectional"))
      (node (ref "U1") (pin "7") (pinfunction "B_7") (pintype "input"))
    )
    (net (code "34") (name "Net-(U1-Y)") (class "Default")
      (node (ref "JP2") (pin "5") (pinfunction "5_5") (pintype "passive"))
      (node (ref "RS485_INPUT") (pin "6") (pinfunction "6_6") (pintype "bidirectional"))
      (node (ref "RS485_OUTPUT") (pin "2") (pinfunction "2_2") (pintype "bidirectional"))
      (node (ref "U1") (pin "5") (pinfunction "Y_5") (pintype "output"))
    )
    (net (code "35") (name "Net-(U1-Z)") (class "Default")
      (node (ref "R9") (pin "1") (pinfunction "1_1") (pintype "passive"))
      (node (ref "RS485_INPUT") (pin "3") (pinfunction "3_3") (pintype "bidirectional"))
      (node (ref "RS485_OUTPUT") (pin "1") (pinfunction "1_1") (pintype "bidirectional"))
      (node (ref "U1") (pin "6") (pinfunction "Z_6") (pintype "output"))
    )
    (net (code "36") (name "Net-(U2-FB)") (class "Default")
      (node (ref "R11") (pin "1") (pinfunction "1_1") (pintype "passive"))
      (node (ref "R12") (pin "2") (pinfunction "2_2") (pintype "passive"))
      (node (ref "U2") (pin "SET_FB") (pinfunction "FB_SET_FB") (pintype "passive"))
    )
    (net (code "37") (name "Net-(U4-FB)") (class "Default")
      (node (ref "R13") (pin "1") (pinfunction "1_1") (pintype "passive"))
      (node (ref "R14") (pin "2") (pinfunction "2_2") (pintype "passive"))
      (node (ref "U4") (pin "SET_FB") (pinfunction "FB_SET_FB") (pintype "passive"))
    )
    (net (code "38") (name "Net-(U11-CH1_IN)") (class "Default")
      (node (ref "J401") (pin "D+") (pinfunction "D+_D+") (pintype "input"))
      (node (ref "U11") (pin "3") (pinfunction "CH1_IN_3") (pintype "input"))
    )
    (net (code "39") (name "Net-(U11-CH1_OUT)") (class "Default")
      (node (ref "R4") (pin "1") (pinfunction "1_1") (pintype "passive"))
      (node (ref "U11") (pin "1") (pinfunction "CH1_OUT_1") (pintype "output"))
    )
    (net (code "40") (name "Net-(U11-CH2_IN)") (class "Default")
      (node (ref "J401") (pin "D-") (pinfunction "D-_D-") (pintype "input"))
      (node (ref "U11") (pin "4") (pinfunction "CH2_IN_4") (pintype "input"))
    )
    (net (code "41") (name "Net-(U11-CH2_OUT)") (class "Default")
      (node (ref "R5") (pin "1") (pinfunction "1_1") (pintype "passive"))
      (node (ref "U11") (pin "6") (pinfunction "CH2_OUT_6") (pintype "output"))
    )
    (net (code "42") (name "POWER_SELECTION") (class "Default")
      (node (ref "C4") (pin "1") (pinfunction "1_1") (pintype "passive"))
      (node (ref "C403") (pin "+") (pinfunction "+_+") (pintype "passive"))
      (node (ref "C9") (pin "1") (pinfunction "1_1") (pintype "passive"))
      (node (ref "D3") (pin "C") (pinfunction "C_C") (pintype "passive"))
      (node (ref "JP1") (pin "1") (pinfunction "1_1") (pintype "passive"))
      (node (ref "JP1") (pin "3") (pinfunction "3_3") (pintype "passive"))
      (node (ref "JP1") (pin "5") (pinfunction "5_5") (pintype "passive"))
      (node (ref "JP2") (pin "3") (pinfunction "3_3") (pintype "passive"))
      (node (ref "U2") (pin "EN") (pinfunction "EN_EN") (pintype "input"))
      (node (ref "U2") (pin "IN1") (pinfunction "IN_IN1") (pintype "power_in"))
      (node (ref "U2") (pin "IN2") (pinfunction "IN_IN2") (pintype "power_in"))
      (node (ref "U2") (pin "IN_CP") (pinfunction "IN(CP)_IN_CP") (pintype "power_in"))
      (node (ref "U4") (pin "EN") (pinfunction "EN_EN") (pintype "input"))
      (node (ref "U4") (pin "IN1") (pinfunction "IN_IN1") (pintype "power_in"))
      (node (ref "U4") (pin "IN2") (pinfunction "IN_IN2") (pintype "power_in"))
      (node (ref "U4") (pin "IN_CP") (pinfunction "IN(CP)_IN_CP") (pintype "power_in"))
    )
    (net (code "43") (name "RS485_RX") (class "Default")
      (node (ref "U1") (pin "2") (pinfunction "R_2") (pintype "output"))
      (node (ref "U3") (pin "52") (pinfunction "52_52") (pintype "bidirectional"))
    )
    (net (code "44") (name "RS485_TX") (class "Default")
      (node (ref "U1") (pin "3") (pinfunction "D_3") (pintype "input"))
      (node (ref "U3") (pin "51") (pinfunction "51_51") (pintype "bidirectional"))
    )
    (net (code "45") (name "RS485_VBUS") (class "Default")
      (node (ref "JP1") (pin "4") (pinfunction "4_4") (pintype "passive"))
      (node (ref "RS485_INPUT") (pin "4") (pinfunction "4_4") (pintype "bidirectional"))
      (node (ref "RS485_INPUT") (pin "5") (pinfunction "5_5") (pintype "bidirectional"))
    )
    (net (code "46") (name "RST{slash}SBWTDIO") (class "Default")
      (node (ref "C8") (pin "1") (pinfunction "1_1") (pintype "passive"))
      (node (ref "J1") (pin "11") (pinfunction "11_11") (pintype "passive"))
      (node (ref "R3") (pin "1") (pinfunction "1_1") (pintype "passive"))
      (node (ref "S1") (pin "2") (pinfunction "S_2") (pintype "passive"))
      (node (ref "U3") (pin "76") (pinfunction "76_76") (pintype "bidirectional"))
    )
    (net (code "47") (name "SENSOR_LED") (class "Default")
      (node (ref "R24") (pin "2") (pinfunction "2_2") (pintype "passive"))
      (node (ref "U3") (pin "3") (pinfunction "3_3") (pintype "bidirectional"))
    )
    (net (code "48") (name "TARGET_PUR") (class "Default")
      (node (ref "R7") (pin "2") (pinfunction "2_2") (pintype "passive"))
      (node (ref "R8") (pin "2") (pinfunction "2_2") (pintype "passive"))
      (node (ref "U3") (pin "63") (pinfunction "63_63") (pintype "bidirectional"))
    )
    (net (code "49") (name "TCK") (class "Default")
      (node (ref "J1") (pin "7") (pinfunction "7_7") (pintype "passive"))
      (node (ref "U3") (pin "75") (pinfunction "75_75") (pintype "bidirectional"))
    )
    (net (code "50") (name "TDI") (class "Default")
      (node (ref "J1") (pin "3") (pinfunction "3_3") (pintype "passive"))
      (node (ref "U3") (pin "73") (pinfunction "73_73") (pintype "bidirectional"))
    )
    (net (code "51") (name "TDO") (class "Default")
      (node (ref "J1") (pin "1") (pinfunction "1_1") (pintype "passive"))
      (node (ref "U3") (pin "72") (pinfunction "72_72") (pintype "bidirectional"))
    )
    (net (code "52") (name "TEST{slash}SBWTCK") (class "Default")
      (node (ref "J1") (pin "8") (pinfunction "8_8") (pintype "passive"))
      (node (ref "U3") (pin "71") (pinfunction "71_71") (pintype "input"))
    )
    (net (code "53") (name "TMS") (class "Default")
      (node (ref "J1") (pin "5") (pinfunction "5_5") (pintype "passive"))
      (node (ref "U3") (pin "74") (pinfunction "74_74") (pintype "bidirectional"))
    )
    (net (code "54") (name "USB_DM") (class "Default")
      (node (ref "C21") (pin "1") (pinfunction "P$1_1") (pintype "passive"))
      (node (ref "R5") (pin "2") (pinfunction "2_2") (pintype "passive"))
      (node (ref "U3") (pin "64") (pinfunction "64_64") (pintype "bidirectional"))
    )
    (net (code "55") (name "USB_DP") (class "Default")
      (node (ref "C18") (pin "1") (pinfunction "P$1_1") (pintype "passive"))
      (node (ref "R4") (pin "2") (pinfunction "2_2") (pintype "passive"))
      (node (ref "U3") (pin "62") (pinfunction "62_62") (pintype "bidirectional"))
    )
    (net (code "56") (name "USB_VBUS") (class "Default")
      (node (ref "C402") (pin "1") (pinfunction "1_1") (pintype "passive"))
      (node (ref "J401") (pin "VBUS") (pinfunction "VBUS_VBUS") (pintype "input"))
      (node (ref "JP1") (pin "2") (pinfunction "2_2") (pintype "passive"))
      (node (ref "S2") (pin "1") (pinfunction "P_1") (pintype "passive"))
      (node (ref "U11") (pin "5") (pinfunction "VCC_5") (pintype "power_in"))
      (node (ref "U3") (pin "65") (pinfunction "65_65") (pintype "power_in"))
    )
    (net (code "57") (name "VCC") (class "Default")
      (node (ref "C12") (pin "1") (pinfunction "1_1") (pintype "passive"))
      (node (ref "C15") (pin "1") (pinfunction "1_1") (pintype "passive"))
      (node (ref "C2") (pin "1") (pinfunction "1_1") (pintype "passive"))
      (node (ref "C24") (pin "1") (pinfunction "1_1") (pintype "passive"))
      (node (ref "C6") (pin "1") (pinfunction "1_1") (pintype "passive"))
      (node (ref "J1") (pin "4") (pinfunction "4_4") (pintype "passive"))
      (node (ref "R1") (pin "2") (pinfunction "2_2") (pintype "passive"))
      (node (ref "R3") (pin "2") (pinfunction "2_2") (pintype "passive"))
      (node (ref "U1") (pin "1") (pinfunction "VCC_1") (pintype "power_in"))
      (node (ref "U3") (pin "18") (pinfunction "18_18") (pintype "power_in"))
      (node (ref "U3") (pin "50") (pinfunction "50_50") (pintype "power_in"))
      (node (ref "U4") (pin "OUT1") (pinfunction "OUT_OUT1") (pintype "power_in"))
      (node (ref "U4") (pin "OUT2") (pinfunction "OUT_OUT2") (pintype "power_in"))
      (node (ref "U4") (pin "OUT_FB") (pinfunction "OUT(FB)_OUT_FB") (pintype "power_in"))
      (node (ref "U5") (pin "DVDD") (pinfunction "DVDD_DVDD") (pintype "power_in"))
    )
    (net (code "58") (name "VCC_5V") (class "Default")
      (node (ref "C14") (pin "2") (pinfunction "2_2") (pintype "passive"))
      (node (ref "C7") (pin "1") (pinfunction "1_1") (pintype "passive"))
      (node (ref "JP3") (pin "1") (pinfunction "1_1") (pintype "passive"))
      (node (ref "R15") (pin "2") (pinfunction "2_2") (pintype "passive"))
      (node (ref "U2") (pin "OUT1") (pinfunction "OUT_OUT1") (pintype "power_in"))
      (node (ref "U2") (pin "OUT2") (pinfunction "OUT_OUT2") (pintype "power_in"))
      (node (ref "U2") (pin "OUT_FB") (pinfunction "OUT(FB)_OUT_FB") (pintype "power_in"))
      (node (ref "U5") (pin "AVDD") (pinfunction "AVDD_AVDD") (pintype "power_in"))
    )
    (net (code "59") (name "unconnected-(J1-Pad2)") (class "Default")
      (node (ref "J1") (pin "2") (pinfunction "2_2") (pintype "passive"))
    )
    (net (code "60") (name "unconnected-(J1-Pad6)") (class "Default")
      (node (ref "J1") (pin "6") (pinfunction "6_6") (pintype "passive"))
    )
    (net (code "61") (name "unconnected-(J1-Pad10)") (class "Default")
      (node (ref "J1") (pin "10") (pinfunction "10_10") (pintype "passive"))
    )
    (net (code "62") (name "unconnected-(J1-Pad12)") (class "Default")
      (node (ref "J1") (pin "12") (pinfunction "12_12") (pintype "passive"))
    )
    (net (code "63") (name "unconnected-(J1-Pad13)") (class "Default")
      (node (ref "J1") (pin "13") (pinfunction "13_13") (pintype "passive"))
    )
    (net (code "64") (name "unconnected-(J1-Pad14)") (class "Default")
      (node (ref "J1") (pin "14") (pinfunction "14_14") (pintype "passive"))
    )
    (net (code "65") (name "unconnected-(J3-PadGNDBREAK)") (class "Default")
      (node (ref "J3") (pin "GNDBREAK") (pinfunction "GNDBREAK_GNDBREAK") (pintype "bidirectional"))
    )
    (net (code "66") (name "unconnected-(J401-PadNC)") (class "Default")
      (node (ref "J401") (pin "NC") (pinfunction "NC_NC") (pintype "input"))
    )
    (net (code "67") (name "unconnected-(U3-Pad1)") (class "Default")
      (node (ref "U3") (pin "1") (pinfunction "1_1") (pintype "bidirectional"))
    )
    (net (code "68") (name "unconnected-(U3-Pad2)") (class "Default")
      (node (ref "U3") (pin "2") (pinfunction "2_2") (pintype "bidirectional"))
    )
    (net (code "69") (name "unconnected-(U3-Pad5)") (class "Default")
      (node (ref "U3") (pin "5") (pinfunction "5_5") (pintype "bidirectional"))
    )
    (net (code "70") (name "unconnected-(U3-Pad6)") (class "Default")
      (node (ref "U3") (pin "6") (pinfunction "6_6") (pintype "bidirectional"))
    )
    (net (code "71") (name "unconnected-(U3-Pad7)") (class "Default")
      (node (ref "U3") (pin "7") (pinfunction "7_7") (pintype "bidirectional"))
    )
    (net (code "72") (name "unconnected-(U3-Pad8)") (class "Default")
      (node (ref "U3") (pin "8") (pinfunction "8_8") (pintype "bidirectional"))
    )
    (net (code "73") (name "unconnected-(U3-Pad9)") (class "Default")
      (node (ref "U3") (pin "9") (pinfunction "9_9") (pintype "bidirectional"))
    )
    (net (code "74") (name "unconnected-(U3-Pad10)") (class "Default")
      (node (ref "U3") (pin "10") (pinfunction "10_10") (pintype "bidirectional"))
    )
    (net (code "75") (name "unconnected-(U3-Pad12)") (class "Default")
      (node (ref "U3") (pin "12") (pinfunction "12_12") (pintype "bidirectional"))
    )
    (net (code "76") (name "unconnected-(U3-Pad13)") (class "Default")
      (node (ref "U3") (pin "13") (pinfunction "13_13") (pintype "bidirectional"))
    )
    (net (code "77") (name "unconnected-(U3-Pad15)") (class "Default")
      (node (ref "U3") (pin "15") (pinfunction "15_15") (pintype "bidirectional"))
    )
    (net (code "78") (name "unconnected-(U3-Pad16)") (class "Default")
      (node (ref "U3") (pin "16") (pinfunction "16_16") (pintype "bidirectional"))
    )
    (net (code "79") (name "unconnected-(U3-Pad17)") (class "Default")
      (node (ref "U3") (pin "17") (pinfunction "17_17") (pintype "bidirectional"))
    )
    (net (code "80") (name "unconnected-(U3-Pad21)") (class "Default")
      (node (ref "U3") (pin "21") (pinfunction "21_21") (pintype "bidirectional"))
    )
    (net (code "81") (name "unconnected-(U3-Pad22)") (class "Default")
      (node (ref "U3") (pin "22") (pinfunction "22_22") (pintype "bidirectional"))
    )
    (net (code "82") (name "unconnected-(U3-Pad23)") (class "Default")
      (node (ref "U3") (pin "23") (pinfunction "23_23") (pintype "bidirectional"))
    )
    (net (code "83") (name "unconnected-(U3-Pad24)") (class "Default")
      (node (ref "U3") (pin "24") (pinfunction "24_24") (pintype "bidirectional"))
    )
    (net (code "84") (name "unconnected-(U3-Pad25)") (class "Default")
      (node (ref "U3") (pin "25") (pinfunction "25_25") (pintype "bidirectional"))
    )
    (net (code "85") (name "unconnected-(U3-Pad26)") (class "Default")
      (node (ref "U3") (pin "26") (pinfunction "26_26") (pintype "bidirectional"))
    )
    (net (code "86") (name "unconnected-(U3-Pad27)") (class "Default")
      (node (ref "U3") (pin "27") (pinfunction "27_27") (pintype "bidirectional"))
    )
    (net (code "87") (name "unconnected-(U3-Pad28)") (class "Default")
      (node (ref "U3") (pin "28") (pinfunction "28_28") (pintype "bidirectional"))
    )
    (net (code "88") (name "unconnected-(U3-Pad29)") (class "Default")
      (node (ref "U3") (pin "29") (pinfunction "29_29") (pintype "bidirectional"))
    )
    (net (code "89") (name "unconnected-(U3-Pad30)") (class "Default")
      (node (ref "U3") (pin "30") (pinfunction "30_30") (pintype "bidirectional"))
    )
    (net (code "90") (name "unconnected-(U3-Pad31)") (class "Default")
      (node (ref "U3") (pin "31") (pinfunction "31_31") (pintype "bidirectional"))
    )
    (net (code "91") (name "unconnected-(U3-Pad32)") (class "Default")
      (node (ref "U3") (pin "32") (pinfunction "32_32") (pintype "bidirectional"))
    )
    (net (code "92") (name "unconnected-(U3-Pad33)") (class "Default")
      (node (ref "U3") (pin "33") (pinfunction "33_33") (pintype "bidirectional"))
    )
    (net (code "93") (name "unconnected-(U3-Pad34)") (class "Default")
      (node (ref "U3") (pin "34") (pinfunction "34_34") (pintype "bidirectional"))
    )
    (net (code "94") (name "unconnected-(U3-Pad35)") (class "Default")
      (node (ref "U3") (pin "35") (pinfunction "35_35") (pintype "bidirectional"))
    )
    (net (code "95") (name "unconnected-(U3-Pad36)") (class "Default")
      (node (ref "U3") (pin "36") (pinfunction "36_36") (pintype "bidirectional"))
    )
    (net (code "96") (name "unconnected-(U3-Pad37)") (class "Default")
      (node (ref "U3") (pin "37") (pinfunction "37_37") (pintype "bidirectional"))
    )
    (net (code "97") (name "unconnected-(U3-Pad40)") (class "Default")
      (node (ref "U3") (pin "40") (pinfunction "40_40") (pintype "bidirectional"))
    )
    (net (code "98") (name "unconnected-(U3-Pad41)") (class "Default")
      (node (ref "U3") (pin "41") (pinfunction "41_41") (pintype "bidirectional"))
    )
    (net (code "99") (name "unconnected-(U3-Pad42)") (class "Default")
      (node (ref "U3") (pin "42") (pinfunction "42_42") (pintype "bidirectional"))
    )
    (net (code "100") (name "unconnected-(U3-Pad43)") (class "Default")
      (node (ref "U3") (pin "43") (pinfunction "43_43") (pintype "bidirectional"))
    )
    (net (code "101") (name "unconnected-(U3-Pad44)") (class "Default")
      (node (ref "U3") (pin "44") (pinfunction "44_44") (pintype "bidirectional"))
    )
    (net (code "102") (name "unconnected-(U3-Pad45)") (class "Default")
      (node (ref "U3") (pin "45") (pinfunction "45_45") (pintype "bidirectional"))
    )
    (net (code "103") (name "unconnected-(U3-Pad46)") (class "Default")
      (node (ref "U3") (pin "46") (pinfunction "46_46") (pintype "bidirectional"))
    )
    (net (code "104") (name "unconnected-(U3-Pad47)") (class "Default")
      (node (ref "U3") (pin "47") (pinfunction "47_47") (pintype "bidirectional"))
    )
    (net (code "105") (name "unconnected-(U3-Pad48)") (class "Default")
      (node (ref "U3") (pin "48") (pinfunction "48_48") (pintype "bidirectional"))
    )
    (net (code "106") (name "unconnected-(U3-Pad53)") (class "Default")
      (node (ref "U3") (pin "53") (pinfunction "53_53") (pintype "bidirectional"))
    )
    (net (code "107") (name "unconnected-(U3-Pad54)") (class "Default")
      (node (ref "U3") (pin "54") (pinfunction "54_54") (pintype "bidirectional"))
    )
    (net (code "108") (name "unconnected-(U3-Pad55)") (class "Default")
      (node (ref "U3") (pin "55") (pinfunction "55_55") (pintype "bidirectional"))
    )
    (net (code "109") (name "unconnected-(U3-Pad56)") (class "Default")
      (node (ref "U3") (pin "56") (pinfunction "56_56") (pintype "bidirectional"))
    )
    (net (code "110") (name "unconnected-(U3-Pad57)") (class "Default")
      (node (ref "U3") (pin "57") (pinfunction "57_57") (pintype "bidirectional"))
    )
    (net (code "111") (name "unconnected-(U3-Pad58)") (class "Default")
      (node (ref "U3") (pin "58") (pinfunction "58_58") (pintype "bidirectional"))
    )
    (net (code "112") (name "unconnected-(U3-Pad77)") (class "Default")
      (node (ref "U3") (pin "77") (pinfunction "77_77") (pintype "bidirectional"))
    )
    (net (code "113") (name "unconnected-(U3-Pad78)") (class "Default")
      (node (ref "U3") (pin "78") (pinfunction "78_78") (pintype "bidirectional"))
    )
    (net (code "114") (name "unconnected-(U3-Pad79)") (class "Default")
      (node (ref "U3") (pin "79") (pinfunction "79_79") (pintype "bidirectional"))
    )
    (net (code "115") (name "unconnected-(U3-Pad80)") (class "Default")
      (node (ref "U3") (pin "80") (pinfunction "80_80") (pintype "bidirectional"))
    )
  )
)
